# rc2usb.net
KiCad netlist of a schematic drawn in EAGLE
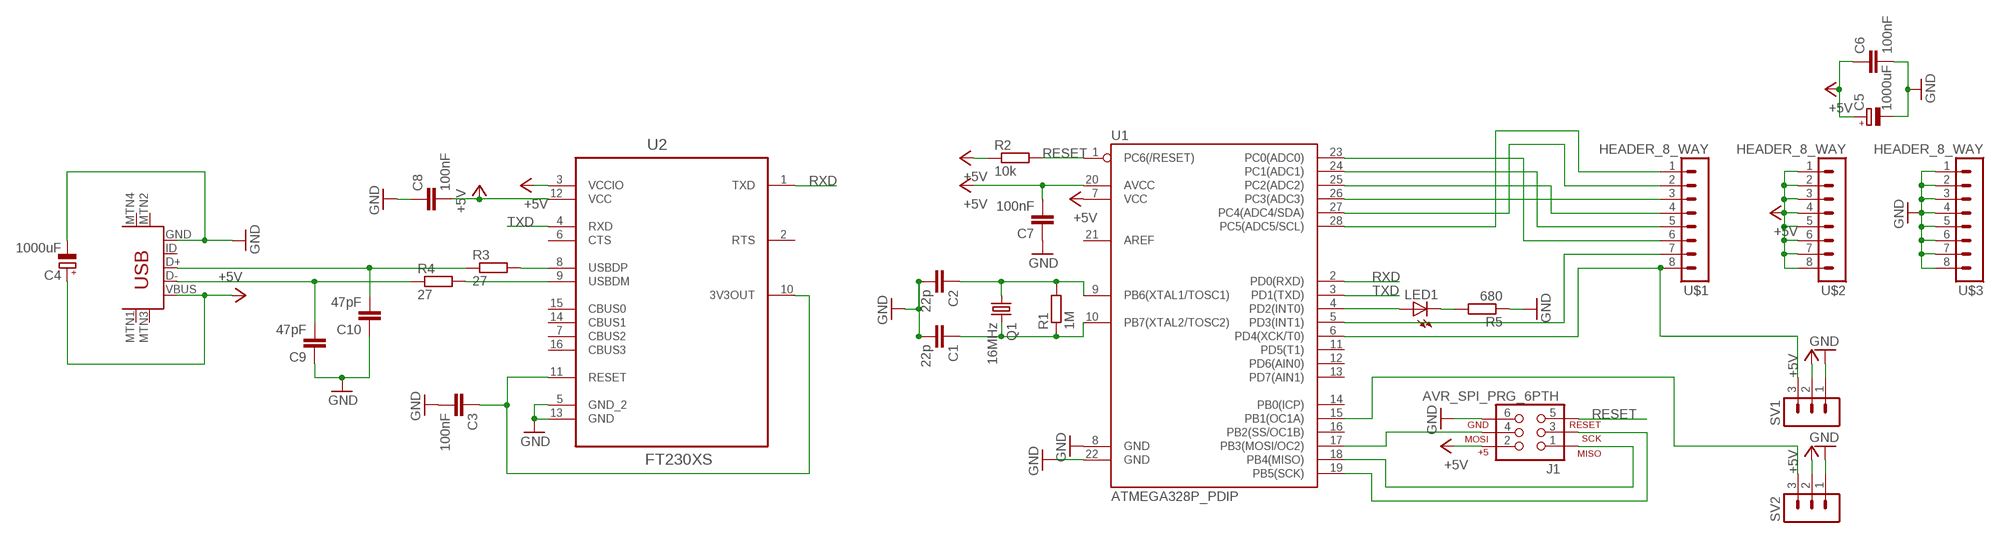
[diagram p0: schematic, sheet 1]

(export (version "E")
  (design (tool "Eeschema 10.0.6"))
  (components
    (comp (ref "C1")
      (value "22p")
      (footprint "eagle-import:C025-040X050")
      (libsource (lib "eagle-import") (part "resistor_C-EU025-040X050"))
    )
    (comp (ref "C2")
      (value "22p")
      (footprint "eagle-import:C025-040X050")
      (libsource (lib "eagle-import") (part "resistor_C-EU025-040X050"))
    )
    (comp (ref "C3")
      (value "100nF")
      (footprint "eagle-import:C025-030X050")
      (libsource (lib "eagle-import") (part "C-EU025-030X050"))
    )
    (comp (ref "C4")
      (value "1000uF")
      (footprint "eagle-import:E5-10,5")
      (libsource (lib "eagle-import") (part "CPOL-EUE5-10.5"))
    )
    (comp (ref "C5")
      (value "1000uF")
      (footprint "eagle-import:E5-10,5")
      (libsource (lib "eagle-import") (part "CPOL-EUE5-10.5"))
    )
    (comp (ref "C6")
      (value "100nF")
      (footprint "eagle-import:C025-030X050")
      (libsource (lib "eagle-import") (part "C-EU025-030X050"))
    )
    (comp (ref "C7")
      (value "100nF")
      (footprint "eagle-import:C025-030X050")
      (libsource (lib "eagle-import") (part "C-EU025-030X050"))
    )
    (comp (ref "C8")
      (value "100nF")
      (footprint "eagle-import:C025-030X050")
      (libsource (lib "eagle-import") (part "C-EU025-030X050"))
    )
    (comp (ref "C9")
      (value "47pF")
      (footprint "eagle-import:C025-030X050")
      (libsource (lib "eagle-import") (part "C-EU025-030X050"))
    )
    (comp (ref "C10")
      (value "47pF")
      (footprint "eagle-import:C025-030X050")
      (libsource (lib "eagle-import") (part "C-EU025-030X050"))
    )
    (comp (ref "J1")
      (value "AVR_SPI_PRG_6PTH")
      (footprint "eagle-import:2X3")
      (libsource (lib "eagle-import") (part "AVR_SPI_PRG_6PTH"))
    )
    (comp (ref "LED1")
      (value "LED5MM")
      (footprint "eagle-import:LED5MM")
      (libsource (lib "eagle-import") (part "LED5MM"))
    )
    (comp (ref "Q1")
      (value "16MHz")
      (footprint "eagle-import:HC49U70")
      (libsource (lib "eagle-import") (part "CRYSTALHC49U70"))
    )
    (comp (ref "R1")
      (value "1M")
      (footprint "eagle-import:0207_10")
      (libsource (lib "eagle-import") (part "R-EU_0207/10"))
    )
    (comp (ref "R2")
      (value "10k")
      (footprint "eagle-import:0207_10")
      (libsource (lib "eagle-import") (part "R-EU_0207/10"))
    )
    (comp (ref "R3")
      (value "27")
      (footprint "eagle-import:0207_10")
      (libsource (lib "eagle-import") (part "R-EU_0207/10"))
    )
    (comp (ref "R4")
      (value "27")
      (footprint "eagle-import:0207_10")
      (libsource (lib "eagle-import") (part "R-EU_0207/10"))
    )
    (comp (ref "R5")
      (value "680")
      (footprint "eagle-import:0207_10")
      (libsource (lib "eagle-import") (part "R-EU_0207/10"))
    )
    (comp (ref "SV1")
      (value "MA03-1")
      (footprint "eagle-import:MA03-1")
      (libsource (lib "eagle-import") (part "MA03-1"))
    )
    (comp (ref "SV2")
      (value "MA03-1")
      (footprint "eagle-import:MA03-1")
      (libsource (lib "eagle-import") (part "MA03-1"))
    )
    (comp (ref "U$1")
      (value "HEADER_8_WAY")
      (footprint "eagle-import:HEADER_8_WAY")
      (libsource (lib "eagle-import") (part "HEADER_8_WAY"))
    )
    (comp (ref "U$2")
      (value "HEADER_8_WAY")
      (footprint "eagle-import:HEADER_8_WAY")
      (libsource (lib "eagle-import") (part "HEADER_8_WAY"))
    )
    (comp (ref "U$3")
      (value "HEADER_8_WAY")
      (footprint "eagle-import:HEADER_8_WAY")
      (libsource (lib "eagle-import") (part "HEADER_8_WAY"))
    )
    (comp (ref "U$4")
      (value "USB-MINIB-5PIN")
      (footprint "eagle-import:USB-MINIB")
      (libsource (lib "eagle-import") (part "USB-MINIB-5PIN"))
    )
    (comp (ref "U1")
      (value "ATMEGA328P_PDIP")
      (footprint "eagle-import:DIL28-3")
      (libsource (lib "eagle-import") (part "ATMEGA328P_PDIP"))
    )
    (comp (ref "U2")
      (value "FT230XS")
      (footprint "eagle-import:SOP63P600X175-16N")
      (libsource (lib "eagle-import") (part "FT230XS"))
    )
  )
  (nets
    (net (code "1") (name "+5V") (class "Default")
      (node (ref "C4") (pin "+") (pinfunction "+_+") (pintype "passive"))
      (node (ref "C5") (pin "+") (pinfunction "+_+") (pintype "passive"))
      (node (ref "C6") (pin "1") (pinfunction "1_1") (pintype "passive"))
      (node (ref "C7") (pin "2") (pinfunction "2_2") (pintype "passive"))
      (node (ref "C8") (pin "2") (pinfunction "2_2") (pintype "passive"))
      (node (ref "J1") (pin "2") (pinfunction "2_2") (pintype "passive"))
      (node (ref "R2") (pin "1") (pinfunction "1_1") (pintype "passive"))
      (node (ref "SV1") (pin "2") (pinfunction "2_2") (pintype "passive"))
      (node (ref "SV2") (pin "2") (pinfunction "2_2") (pintype "passive"))
      (node (ref "U$2") (pin "1") (pinfunction "1_1") (pintype "passive"))
      (node (ref "U$2") (pin "2") (pinfunction "2_2") (pintype "passive"))
      (node (ref "U$2") (pin "3") (pinfunction "3_3") (pintype "passive"))
      (node (ref "U$2") (pin "4") (pinfunction "4_4") (pintype "passive"))
      (node (ref "U$2") (pin "5") (pinfunction "5_5") (pintype "passive"))
      (node (ref "U$2") (pin "6") (pinfunction "6_6") (pintype "passive"))
      (node (ref "U$2") (pin "7") (pinfunction "7_7") (pintype "passive"))
      (node (ref "U$2") (pin "8") (pinfunction "8_8") (pintype "passive"))
      (node (ref "U$4") (pin "VBUS") (pinfunction "VBUS_VBUS") (pintype "bidirectional"))
      (node (ref "U1") (pin "20") (pinfunction "AVCC_20") (pintype "bidirectional"))
      (node (ref "U1") (pin "7") (pinfunction "VCC_7") (pintype "bidirectional"))
      (node (ref "U2") (pin "12") (pinfunction "VCC_12") (pintype "output"))
      (node (ref "U2") (pin "3") (pinfunction "VCCIO_3") (pintype "power_in"))
    )
    (net (code "2") (name "/RESET") (class "Default")
      (node (ref "J1") (pin "5") (pinfunction "5_5") (pintype "passive"))
      (node (ref "R2") (pin "2") (pinfunction "2_2") (pintype "passive"))
      (node (ref "U1") (pin "1") (pinfunction "PC6(/RESET)_1") (pintype "bidirectional"))
    )
    (net (code "3") (name "/RXD") (class "Default")
      (node (ref "U1") (pin "2") (pinfunction "PD0(RXD)_2") (pintype "bidirectional"))
      (node (ref "U2") (pin "1") (pinfunction "TXD_1") (pintype "output"))
    )
    (net (code "4") (name "/TXD") (class "Default")
      (node (ref "U1") (pin "3") (pinfunction "PD1(TXD)_3") (pintype "bidirectional"))
      (node (ref "U2") (pin "4") (pinfunction "RXD_4") (pintype "input"))
    )
    (net (code "5") (name "GND") (class "Default")
      (node (ref "C1") (pin "2") (pinfunction "2_2") (pintype "passive"))
      (node (ref "C10") (pin "1") (pinfunction "1_1") (pintype "passive"))
      (node (ref "C2") (pin "2") (pinfunction "2_2") (pintype "passive"))
      (node (ref "C3") (pin "2") (pinfunction "2_2") (pintype "passive"))
      (node (ref "C4") (pin "-") (pinfunction "-_-") (pintype "passive"))
      (node (ref "C5") (pin "-") (pinfunction "-_-") (pintype "passive"))
      (node (ref "C6") (pin "2") (pinfunction "2_2") (pintype "passive"))
      (node (ref "C7") (pin "1") (pinfunction "1_1") (pintype "passive"))
      (node (ref "C8") (pin "1") (pinfunction "1_1") (pintype "passive"))
      (node (ref "C9") (pin "1") (pinfunction "1_1") (pintype "passive"))
      (node (ref "J1") (pin "6") (pinfunction "6_6") (pintype "passive"))
      (node (ref "R5") (pin "1") (pinfunction "1_1") (pintype "passive"))
      (node (ref "SV1") (pin "1") (pinfunction "1_1") (pintype "passive"))
      (node (ref "SV2") (pin "1") (pinfunction "1_1") (pintype "passive"))
      (node (ref "U$3") (pin "1") (pinfunction "1_1") (pintype "passive"))
      (node (ref "U$3") (pin "2") (pinfunction "2_2") (pintype "passive"))
      (node (ref "U$3") (pin "3") (pinfunction "3_3") (pintype "passive"))
      (node (ref "U$3") (pin "4") (pinfunction "4_4") (pintype "passive"))
      (node (ref "U$3") (pin "5") (pinfunction "5_5") (pintype "passive"))
      (node (ref "U$3") (pin "6") (pinfunction "6_6") (pintype "passive"))
      (node (ref "U$3") (pin "7") (pinfunction "7_7") (pintype "passive"))
      (node (ref "U$3") (pin "8") (pinfunction "8_8") (pintype "passive"))
      (node (ref "U$4") (pin "GND") (pinfunction "GND_GND") (pintype "bidirectional"))
      (node (ref "U1") (pin "22") (pinfunction "GND_22") (pintype "bidirectional"))
      (node (ref "U1") (pin "8") (pinfunction "GND_8") (pintype "bidirectional"))
      (node (ref "U2") (pin "13") (pinfunction "GND_13") (pintype "power_in"))
      (node (ref "U2") (pin "5") (pinfunction "GND_2_5") (pintype "power_in"))
    )
    (net (code "6") (name "Net-(C9-Pad2)") (class "Default")
      (node (ref "C9") (pin "2") (pinfunction "2_2") (pintype "passive"))
      (node (ref "R4") (pin "1") (pinfunction "1_1") (pintype "passive"))
      (node (ref "U$4") (pin "D-") (pinfunction "D-_D-") (pintype "bidirectional"))
    )
    (net (code "7") (name "Net-(C10-Pad2)") (class "Default")
      (node (ref "C10") (pin "2") (pinfunction "2_2") (pintype "passive"))
      (node (ref "R3") (pin "1") (pinfunction "1_1") (pintype "passive"))
      (node (ref "U$4") (pin "D+") (pinfunction "D+_D+") (pintype "bidirectional"))
    )
    (net (code "8") (name "Net-(LED1-C)") (class "Default")
      (node (ref "LED1") (pin "K") (pinfunction "C_K") (pintype "passive"))
      (node (ref "R5") (pin "2") (pinfunction "2_2") (pintype "passive"))
    )
    (net (code "9") (name "Net-(U1-PB1(OC1A))") (class "Default")
      (node (ref "SV2") (pin "3") (pinfunction "3_3") (pintype "passive"))
      (node (ref "U1") (pin "15") (pinfunction "PB1(OC1A)_15") (pintype "bidirectional"))
    )
    (net (code "10") (name "Net-(U1-PB3(MOSI{slash}OC2))") (class "Default")
      (node (ref "J1") (pin "4") (pinfunction "4_4") (pintype "passive"))
      (node (ref "U1") (pin "17") (pinfunction "PB3(MOSI/OC2)_17") (pintype "bidirectional"))
    )
    (net (code "11") (name "Net-(U1-PB4(MISO))") (class "Default")
      (node (ref "J1") (pin "1") (pinfunction "1_1") (pintype "passive"))
      (node (ref "U1") (pin "18") (pinfunction "PB4(MISO)_18") (pintype "bidirectional"))
    )
    (net (code "12") (name "Net-(U1-PB5(SCK))") (class "Default")
      (node (ref "J1") (pin "3") (pinfunction "3_3") (pintype "passive"))
      (node (ref "U1") (pin "19") (pinfunction "PB5(SCK)_19") (pintype "bidirectional"))
    )
    (net (code "13") (name "Net-(U1-PB6(XTAL1{slash}TOSC1))") (class "Default")
      (node (ref "C2") (pin "1") (pinfunction "1_1") (pintype "passive"))
      (node (ref "Q1") (pin "1") (pinfunction "1_1") (pintype "passive"))
      (node (ref "R1") (pin "2") (pinfunction "2_2") (pintype "passive"))
      (node (ref "U1") (pin "9") (pinfunction "PB6(XTAL1/TOSC1)_9") (pintype "bidirectional"))
    )
    (net (code "14") (name "Net-(U1-PB7(XTAL2{slash}TOSC2))") (class "Default")
      (node (ref "C1") (pin "1") (pinfunction "1_1") (pintype "passive"))
      (node (ref "Q1") (pin "2") (pinfunction "2_2") (pintype "passive"))
      (node (ref "R1") (pin "1") (pinfunction "1_1") (pintype "passive"))
      (node (ref "U1") (pin "10") (pinfunction "PB7(XTAL2/TOSC2)_10") (pintype "bidirectional"))
    )
    (net (code "15") (name "Net-(U1-PC0(ADC0))") (class "Default")
      (node (ref "U$1") (pin "6") (pinfunction "6_6") (pintype "passive"))
      (node (ref "U1") (pin "23") (pinfunction "PC0(ADC0)_23") (pintype "bidirectional"))
    )
    (net (code "16") (name "Net-(U1-PC1(ADC1))") (class "Default")
      (node (ref "U$1") (pin "5") (pinfunction "5_5") (pintype "passive"))
      (node (ref "U1") (pin "24") (pinfunction "PC1(ADC1)_24") (pintype "bidirectional"))
    )
    (net (code "17") (name "Net-(U1-PC2(ADC2))") (class "Default")
      (node (ref "U$1") (pin "4") (pinfunction "4_4") (pintype "passive"))
      (node (ref "U1") (pin "25") (pinfunction "PC2(ADC2)_25") (pintype "bidirectional"))
    )
    (net (code "18") (name "Net-(U1-PC3(ADC3))") (class "Default")
      (node (ref "U$1") (pin "3") (pinfunction "3_3") (pintype "passive"))
      (node (ref "U1") (pin "26") (pinfunction "PC3(ADC3)_26") (pintype "bidirectional"))
    )
    (net (code "19") (name "Net-(U1-PC4(ADC4{slash}SDA))") (class "Default")
      (node (ref "U$1") (pin "2") (pinfunction "2_2") (pintype "passive"))
      (node (ref "U1") (pin "27") (pinfunction "PC4(ADC4/SDA)_27") (pintype "bidirectional"))
    )
    (net (code "20") (name "Net-(U1-PC5(ADC5{slash}SCL))") (class "Default")
      (node (ref "U$1") (pin "1") (pinfunction "1_1") (pintype "passive"))
      (node (ref "U1") (pin "28") (pinfunction "PC5(ADC5/SCL)_28") (pintype "bidirectional"))
    )
    (net (code "21") (name "Net-(U1-PD2(INT0))") (class "Default")
      (node (ref "LED1") (pin "A") (pinfunction "A_A") (pintype "passive"))
      (node (ref "U1") (pin "4") (pinfunction "PD2(INT0)_4") (pintype "bidirectional"))
    )
    (net (code "22") (name "Net-(U1-PD3(INT1))") (class "Default")
      (node (ref "U$1") (pin "7") (pinfunction "7_7") (pintype "passive"))
      (node (ref "U1") (pin "5") (pinfunction "PD3(INT1)_5") (pintype "bidirectional"))
    )
    (net (code "23") (name "Net-(U1-PD4(XCK{slash}T0))") (class "Default")
      (node (ref "SV1") (pin "3") (pinfunction "3_3") (pintype "passive"))
      (node (ref "U$1") (pin "8") (pinfunction "8_8") (pintype "passive"))
      (node (ref "U1") (pin "6") (pinfunction "PD4(XCK/T0)_6") (pintype "bidirectional"))
    )
    (net (code "24") (name "Net-(U2-3V3OUT)") (class "Default")
      (node (ref "C3") (pin "1") (pinfunction "1_1") (pintype "passive"))
      (node (ref "U2") (pin "10") (pinfunction "3V3OUT_10") (pintype "output"))
      (node (ref "U2") (pin "11") (pinfunction "RESET_11") (pintype "input"))
    )
    (net (code "25") (name "Net-(U2-USBDM)") (class "Default")
      (node (ref "R4") (pin "2") (pinfunction "2_2") (pintype "passive"))
      (node (ref "U2") (pin "9") (pinfunction "USBDM_9") (pintype "input"))
    )
    (net (code "26") (name "Net-(U2-USBDP)") (class "Default")
      (node (ref "R3") (pin "2") (pinfunction "2_2") (pintype "passive"))
      (node (ref "U2") (pin "8") (pinfunction "USBDP_8") (pintype "input"))
    )
    (net (code "27") (name "unconnected-(U$4-MTN1-PadMTN3)") (class "Default")
      (node (ref "U$4") (pin "MTN3") (pinfunction "MTN1_MTN3") (pintype "bidirectional"))
    )
    (net (code "28") (name "unconnected-(U$4-MTN2-PadMTN1)") (class "Default")
      (node (ref "U$4") (pin "MTN1") (pinfunction "MTN2_MTN1") (pintype "bidirectional"))
    )
    (net (code "29") (name "unconnected-(U$4-MTN3-PadMTN2)") (class "Default")
      (node (ref "U$4") (pin "MTN2") (pinfunction "MTN3_MTN2") (pintype "bidirectional"))
    )
    (net (code "30") (name "unconnected-(U$4-PadID)") (class "Default")
      (node (ref "U$4") (pin "ID") (pinfunction "ID_ID") (pintype "bidirectional"))
    )
    (net (code "31") (name "unconnected-(U$4-PadMTN4)") (class "Default")
      (node (ref "U$4") (pin "MTN4") (pinfunction "MTN4_MTN4") (pintype "bidirectional"))
    )
    (net (code "32") (name "unconnected-(U1-AREF-Pad21)") (class "Default")
      (node (ref "U1") (pin "21") (pinfunction "AREF_21") (pintype "bidirectional"))
    )
    (net (code "33") (name "unconnected-(U1-PB0(ICP)-Pad14)") (class "Default")
      (node (ref "U1") (pin "14") (pinfunction "PB0(ICP)_14") (pintype "bidirectional"))
    )
    (net (code "34") (name "unconnected-(U1-PB2(SS{slash}OC1B)-Pad16)") (class "Default")
      (node (ref "U1") (pin "16") (pinfunction "PB2(SS/OC1B)_16") (pintype "bidirectional"))
    )
    (net (code "35") (name "unconnected-(U1-PD5(T1)-Pad11)") (class "Default")
      (node (ref "U1") (pin "11") (pinfunction "PD5(T1)_11") (pintype "bidirectional"))
    )
    (net (code "36") (name "unconnected-(U1-PD6(AIN0)-Pad12)") (class "Default")
      (node (ref "U1") (pin "12") (pinfunction "PD6(AIN0)_12") (pintype "bidirectional"))
    )
    (net (code "37") (name "unconnected-(U1-PD7(AIN1)-Pad13)") (class "Default")
      (node (ref "U1") (pin "13") (pinfunction "PD7(AIN1)_13") (pintype "bidirectional"))
    )
    (net (code "38") (name "unconnected-(U2-CBUS0-Pad15)") (class "Default")
      (node (ref "U2") (pin "15") (pinfunction "CBUS0_15") (pintype "input"))
    )
    (net (code "39") (name "unconnected-(U2-CBUS1-Pad14)") (class "Default")
      (node (ref "U2") (pin "14") (pinfunction "CBUS1_14") (pintype "input"))
    )
    (net (code "40") (name "unconnected-(U2-CBUS2-Pad7)") (class "Default")
      (node (ref "U2") (pin "7") (pinfunction "CBUS2_7") (pintype "input"))
    )
    (net (code "41") (name "unconnected-(U2-CBUS3-Pad16)") (class "Default")
      (node (ref "U2") (pin "16") (pinfunction "CBUS3_16") (pintype "input"))
    )
    (net (code "42") (name "unconnected-(U2-CTS-Pad6)") (class "Default")
      (node (ref "U2") (pin "6") (pinfunction "CTS_6") (pintype "input"))
    )
    (net (code "43") (name "unconnected-(U2-RTS-Pad2)") (class "Default")
      (node (ref "U2") (pin "2") (pinfunction "RTS_2") (pintype "output"))
    )
  )
)
